# 8bit_reg_v2.net
KiCad netlist of a schematic drawn in Altium Designer
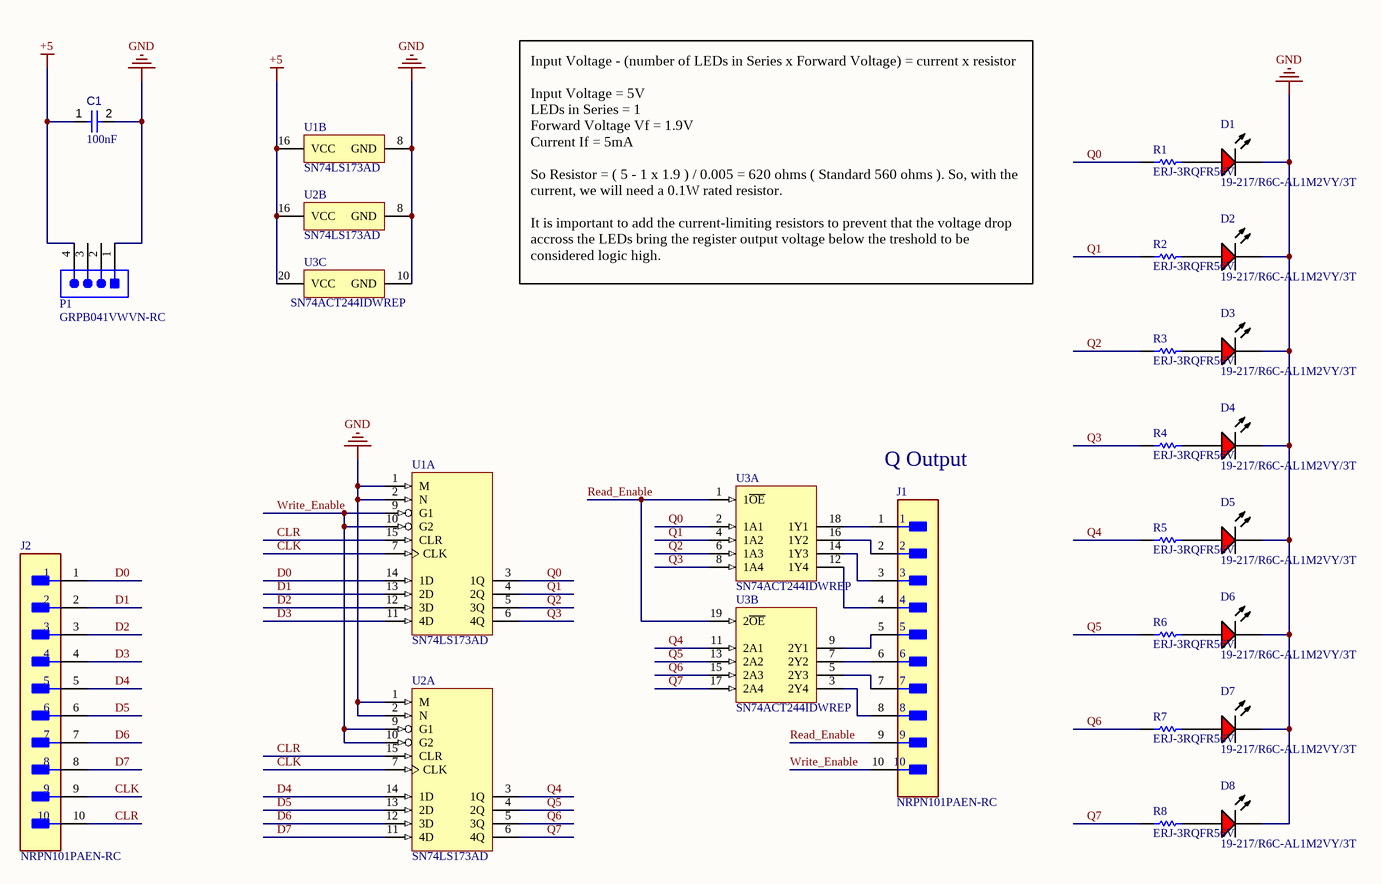
[diagram p0: 8bit_reg_v2.SchDoc]

(export (version "E")
  (design (tool "Eeschema 10.0.6"))
  (components
    (comp (ref "C1")
      (value "100nF")
      (footprint "CAPC1608X90X40NL10T20")
      (description "Chip Capacitor, 100 nF, +/- 10%, 50 V, 0603 (1608 Metric)")
      (fields (field (name "TOLERANCE") "10%") (field (name "Comment") "Capacitor 100 nF +/-10% 50 V 0603"))
      (libsource (lib "GOZ - Altium 365 cloud") (part "CAP-NP-2"))
    )
    (comp (ref "D1")
      (value "19-217/R6C-AL1M2VY/3T")
      (footprint "EVRL-0603-2_V")
      (description "Chip LED, Red, 5 V, 25 mA, -40 to 85 degC, 2-Pin SMD (0603), RoHS, Tape and Reel")
      (fields (field (name "MANUFACTURER") "Everlight Electronics"))
      (libsource (lib "GOZ - Altium 365 cloud") (part "LED-RED-AK-2"))
    )
    (comp (ref "D2")
      (value "19-217/R6C-AL1M2VY/3T")
      (footprint "EVRL-0603-2_V")
      (description "Chip LED, Red, 5 V, 25 mA, -40 to 85 degC, 2-Pin SMD (0603), RoHS, Tape and Reel")
      (fields (field (name "MANUFACTURER") "Everlight Electronics"))
      (libsource (lib "GOZ - Altium 365 cloud") (part "LED-RED-AK-2"))
    )
    (comp (ref "D3")
      (value "19-217/R6C-AL1M2VY/3T")
      (footprint "EVRL-0603-2_V")
      (description "Chip LED, Red, 5 V, 25 mA, -40 to 85 degC, 2-Pin SMD (0603), RoHS, Tape and Reel")
      (fields (field (name "MANUFACTURER") "Everlight Electronics"))
      (libsource (lib "GOZ - Altium 365 cloud") (part "LED-RED-AK-2"))
    )
    (comp (ref "D4")
      (value "19-217/R6C-AL1M2VY/3T")
      (footprint "EVRL-0603-2_V")
      (description "Chip LED, Red, 5 V, 25 mA, -40 to 85 degC, 2-Pin SMD (0603), RoHS, Tape and Reel")
      (fields (field (name "MANUFACTURER") "Everlight Electronics"))
      (libsource (lib "GOZ - Altium 365 cloud") (part "LED-RED-AK-2"))
    )
    (comp (ref "D5")
      (value "19-217/R6C-AL1M2VY/3T")
      (footprint "EVRL-0603-2_V")
      (description "Chip LED, Red, 5 V, 25 mA, -40 to 85 degC, 2-Pin SMD (0603), RoHS, Tape and Reel")
      (fields (field (name "MANUFACTURER") "Everlight Electronics"))
      (libsource (lib "GOZ - Altium 365 cloud") (part "LED-RED-AK-2"))
    )
    (comp (ref "D6")
      (value "19-217/R6C-AL1M2VY/3T")
      (footprint "EVRL-0603-2_V")
      (description "Chip LED, Red, 5 V, 25 mA, -40 to 85 degC, 2-Pin SMD (0603), RoHS, Tape and Reel")
      (fields (field (name "MANUFACTURER") "Everlight Electronics"))
      (libsource (lib "GOZ - Altium 365 cloud") (part "LED-RED-AK-2"))
    )
    (comp (ref "D7")
      (value "19-217/R6C-AL1M2VY/3T")
      (footprint "EVRL-0603-2_V")
      (description "Chip LED, Red, 5 V, 25 mA, -40 to 85 degC, 2-Pin SMD (0603), RoHS, Tape and Reel")
      (fields (field (name "MANUFACTURER") "Everlight Electronics"))
      (libsource (lib "GOZ - Altium 365 cloud") (part "LED-RED-AK-2"))
    )
    (comp (ref "D8")
      (value "19-217/R6C-AL1M2VY/3T")
      (footprint "EVRL-0603-2_V")
      (description "Chip LED, Red, 5 V, 25 mA, -40 to 85 degC, 2-Pin SMD (0603), RoHS, Tape and Reel")
      (fields (field (name "MANUFACTURER") "Everlight Electronics"))
      (libsource (lib "GOZ - Altium 365 cloud") (part "LED-RED-AK-2"))
    )
    (comp (ref "J1")
      (value "NRPN101PAEN-RC")
      (footprint "FP-NRPN101PAEN-RC-MFG")
      (description "CONN HEADER VERT 10POS 2MM")
      (fields
        (field (name "OCTOPART") "https://octopart.com/nrpn101paen-rc-sullins-18674398")
        (field (name "MANUFACTURER") "Sullins")
      )
      (libsource (lib "") (part "aee40dc8b284c03a16094555aa210be_1"))
    )
    (comp (ref "J2")
      (value "NRPN101PAEN-RC")
      (footprint "FP-NRPN101PAEN-RC-MFG")
      (description "CONN HEADER VERT 10POS 2MM")
      (fields
        (field (name "OCTOPART") "https://octopart.com/nrpn101paen-rc-sullins-18674398")
        (field (name "MANUFACTURER") "Sullins")
      )
      (libsource (lib "Altium Content Vault") (part "aee40dc8b284c03a16094555aa210be"))
    )
    (comp (ref "P1")
      (value "GRPB041VWVN-RC")
      (footprint "SLIN-GRPB041VWVN-RC_V")
      (fields (field (name "MANUFACTURER") "Sullins"))
      (libsource (lib "Altium Content Vault") (part "CN-1P-M-R4"))
    )
    (comp (ref "R1")
      (value "ERJ-3RQFR56V")
      (footprint "RESC1608X55X30NL15T15")
      (fields (field (name "MANUFACTURER") "Panasonic"))
      (libsource (lib "Altium Content Vault") (part "RES"))
    )
    (comp (ref "R2")
      (value "ERJ-3RQFR56V")
      (footprint "RESC1608X55X30NL15T15")
      (fields (field (name "MANUFACTURER") "Panasonic"))
      (libsource (lib "Altium Content Vault") (part "RES"))
    )
    (comp (ref "R3")
      (value "ERJ-3RQFR56V")
      (footprint "RESC1608X55X30NL15T15")
      (fields (field (name "MANUFACTURER") "Panasonic"))
      (libsource (lib "Altium Content Vault") (part "RES"))
    )
    (comp (ref "R4")
      (value "ERJ-3RQFR56V")
      (footprint "RESC1608X55X30NL15T15")
      (fields (field (name "MANUFACTURER") "Panasonic"))
      (libsource (lib "Altium Content Vault") (part "RES"))
    )
    (comp (ref "R5")
      (value "ERJ-3RQFR56V")
      (footprint "RESC1608X55X30NL15T15")
      (fields (field (name "MANUFACTURER") "Panasonic"))
      (libsource (lib "Altium Content Vault") (part "RES"))
    )
    (comp (ref "R6")
      (value "ERJ-3RQFR56V")
      (footprint "RESC1608X55X30NL15T15")
      (fields (field (name "MANUFACTURER") "Panasonic"))
      (libsource (lib "Altium Content Vault") (part "RES"))
    )
    (comp (ref "R7")
      (value "ERJ-3RQFR56V")
      (footprint "RESC1608X55X30NL15T15")
      (fields (field (name "MANUFACTURER") "Panasonic"))
      (libsource (lib "Altium Content Vault") (part "RES"))
    )
    (comp (ref "R8")
      (value "ERJ-3RQFR56V")
      (footprint "RESC1608X55X30NL15T15")
      (fields (field (name "MANUFACTURER") "Panasonic"))
      (libsource (lib "Altium Content Vault") (part "RES"))
    )
    (comp (ref "U1")
      (value "SN74LS173AD")
      (footprint "D0016A_M")
      (description "TEXAS INSTRUMENTS SN74LS173AD Flip-Flop, D, 17 ns, 50 MHz, 24 mA, SOIC, 16 Pins")
      (libsource (lib "GOZ - Altium 365 cloud") (part "TI-SNX4XX173X-16"))
    )
    (comp (ref "U2")
      (value "SN74LS173AD")
      (footprint "D0016A_M")
      (description "TEXAS INSTRUMENTS SN74LS173AD Flip-Flop, D, 17 ns, 50 MHz, 24 mA, SOIC, 16 Pins")
      (libsource (lib "GOZ - Altium 365 cloud") (part "TI-SNX4XX173X-16"))
    )
    (comp (ref "U3")
      (value "SN74ACT244IDWREP")
      (footprint "DW0020A_L")
      (description "Enhanced Product Octal Buffers/Drivers With 3-State Outputs, DW0020A, LARGE T&R")
      (fields
        (field (name "GENERIC PART NUMBER") "SN74ACT244-EP")
        (field (name "MANUFACTURER") "Texas Instruments")
      )
      (libsource (lib "SN74ACT244IDWREP") (part "CMP-0440-00699-3"))
    )
  )
  (nets
    (net (code "1") (name "+5") (class "Default")
      (node (ref "C1") (pin "1") (pinfunction "1_1") (pintype "passive"))
      (node (ref "P1") (pin "4") (pinfunction "4_4") (pintype "passive"))
      (node (ref "U1") (pin "16") (pinfunction "VCC_16") (pintype "power_in"))
      (node (ref "U2") (pin "16") (pinfunction "VCC_16") (pintype "power_in"))
      (node (ref "U3") (pin "20") (pinfunction "VCC_20") (pintype "power_in"))
    )
    (net (code "2") (name "/CLK") (class "Default")
      (node (ref "J2") (pin "9") (pinfunction "9_9") (pintype "passive"))
      (node (ref "U1") (pin "7") (pinfunction "CLK_7") (pintype "input"))
      (node (ref "U2") (pin "7") (pinfunction "CLK_7") (pintype "input"))
    )
    (net (code "3") (name "/CLR") (class "Default")
      (node (ref "J2") (pin "10") (pinfunction "10_10") (pintype "passive"))
      (node (ref "U1") (pin "15") (pinfunction "CLR_15") (pintype "input"))
      (node (ref "U2") (pin "15") (pinfunction "CLR_15") (pintype "input"))
    )
    (net (code "4") (name "/D0") (class "Default")
      (node (ref "J2") (pin "1") (pinfunction "1_1") (pintype "passive"))
      (node (ref "U1") (pin "14") (pinfunction "1D_14") (pintype "input"))
    )
    (net (code "5") (name "/D1") (class "Default")
      (node (ref "J2") (pin "2") (pinfunction "2_2") (pintype "passive"))
      (node (ref "U1") (pin "13") (pinfunction "2D_13") (pintype "input"))
    )
    (net (code "6") (name "/D2") (class "Default")
      (node (ref "J2") (pin "3") (pinfunction "3_3") (pintype "passive"))
      (node (ref "U1") (pin "12") (pinfunction "3D_12") (pintype "input"))
    )
    (net (code "7") (name "/D3") (class "Default")
      (node (ref "J2") (pin "4") (pinfunction "4_4") (pintype "passive"))
      (node (ref "U1") (pin "11") (pinfunction "4D_11") (pintype "input"))
    )
    (net (code "8") (name "/D4") (class "Default")
      (node (ref "J2") (pin "5") (pinfunction "5_5") (pintype "passive"))
      (node (ref "U2") (pin "14") (pinfunction "1D_14") (pintype "input"))
    )
    (net (code "9") (name "/D5") (class "Default")
      (node (ref "J2") (pin "6") (pinfunction "6_6") (pintype "passive"))
      (node (ref "U2") (pin "13") (pinfunction "2D_13") (pintype "input"))
    )
    (net (code "10") (name "/D6") (class "Default")
      (node (ref "J2") (pin "7") (pinfunction "7_7") (pintype "passive"))
      (node (ref "U2") (pin "12") (pinfunction "3D_12") (pintype "input"))
    )
    (net (code "11") (name "/D7") (class "Default")
      (node (ref "J2") (pin "8") (pinfunction "8_8") (pintype "passive"))
      (node (ref "U2") (pin "11") (pinfunction "4D_11") (pintype "input"))
    )
    (net (code "12") (name "/Q0") (class "Default")
      (node (ref "R1") (pin "1") (pinfunction "1_1") (pintype "passive"))
      (node (ref "U1") (pin "3") (pinfunction "1Q_3") (pintype "tri_state"))
      (node (ref "U3") (pin "2") (pinfunction "1A1_2") (pintype "input"))
    )
    (net (code "13") (name "/Q1") (class "Default")
      (node (ref "R2") (pin "1") (pinfunction "1_1") (pintype "passive"))
      (node (ref "U1") (pin "4") (pinfunction "2Q_4") (pintype "tri_state"))
      (node (ref "U3") (pin "4") (pinfunction "1A2_4") (pintype "input"))
    )
    (net (code "14") (name "/Q2") (class "Default")
      (node (ref "R3") (pin "1") (pinfunction "1_1") (pintype "passive"))
      (node (ref "U1") (pin "5") (pinfunction "3Q_5") (pintype "tri_state"))
      (node (ref "U3") (pin "6") (pinfunction "1A3_6") (pintype "input"))
    )
    (net (code "15") (name "/Q3") (class "Default")
      (node (ref "R4") (pin "1") (pinfunction "1_1") (pintype "passive"))
      (node (ref "U1") (pin "6") (pinfunction "4Q_6") (pintype "tri_state"))
      (node (ref "U3") (pin "8") (pinfunction "1A4_8") (pintype "input"))
    )
    (net (code "16") (name "/Q4") (class "Default")
      (node (ref "R5") (pin "1") (pinfunction "1_1") (pintype "passive"))
      (node (ref "U2") (pin "3") (pinfunction "1Q_3") (pintype "tri_state"))
      (node (ref "U3") (pin "11") (pinfunction "2A1_11") (pintype "input"))
    )
    (net (code "17") (name "/Q5") (class "Default")
      (node (ref "R6") (pin "1") (pinfunction "1_1") (pintype "passive"))
      (node (ref "U2") (pin "4") (pinfunction "2Q_4") (pintype "tri_state"))
      (node (ref "U3") (pin "13") (pinfunction "2A2_13") (pintype "input"))
    )
    (net (code "18") (name "/Q6") (class "Default")
      (node (ref "R7") (pin "1") (pinfunction "1_1") (pintype "passive"))
      (node (ref "U2") (pin "5") (pinfunction "3Q_5") (pintype "tri_state"))
      (node (ref "U3") (pin "15") (pinfunction "2A3_15") (pintype "input"))
    )
    (net (code "19") (name "/Q7") (class "Default")
      (node (ref "R8") (pin "1") (pinfunction "1_1") (pintype "passive"))
      (node (ref "U2") (pin "6") (pinfunction "4Q_6") (pintype "tri_state"))
      (node (ref "U3") (pin "17") (pinfunction "2A4_17") (pintype "input"))
    )
    (net (code "20") (name "/Read_Enable") (class "Default")
      (node (ref "J1") (pin "9") (pinfunction "9_9") (pintype "passive"))
      (node (ref "U3") (pin "1") (pinfunction "1~{OE}_1") (pintype "input"))
      (node (ref "U3") (pin "19") (pinfunction "2~{OE}_19") (pintype "input"))
    )
    (net (code "21") (name "/Write_Enable") (class "Default")
      (node (ref "J1") (pin "10") (pinfunction "10_10") (pintype "passive"))
      (node (ref "U1") (pin "10") (pinfunction "G2_10") (pintype "input"))
      (node (ref "U1") (pin "9") (pinfunction "G1_9") (pintype "input"))
      (node (ref "U2") (pin "10") (pinfunction "G2_10") (pintype "input"))
      (node (ref "U2") (pin "9") (pinfunction "G1_9") (pintype "input"))
    )
    (net (code "22") (name "GND") (class "Default")
      (node (ref "C1") (pin "2") (pinfunction "2_2") (pintype "passive"))
      (node (ref "D1") (pin "2") (pinfunction "K_2") (pintype "passive"))
      (node (ref "D2") (pin "2") (pinfunction "K_2") (pintype "passive"))
      (node (ref "D3") (pin "2") (pinfunction "K_2") (pintype "passive"))
      (node (ref "D4") (pin "2") (pinfunction "K_2") (pintype "passive"))
      (node (ref "D5") (pin "2") (pinfunction "K_2") (pintype "passive"))
      (node (ref "D6") (pin "2") (pinfunction "K_2") (pintype "passive"))
      (node (ref "D7") (pin "2") (pinfunction "K_2") (pintype "passive"))
      (node (ref "D8") (pin "2") (pinfunction "K_2") (pintype "passive"))
      (node (ref "P1") (pin "1") (pinfunction "1_1") (pintype "passive"))
      (node (ref "U1") (pin "1") (pinfunction "M_1") (pintype "input"))
      (node (ref "U1") (pin "2") (pinfunction "N_2") (pintype "input"))
      (node (ref "U1") (pin "8") (pinfunction "GND_8") (pintype "power_in"))
      (node (ref "U2") (pin "1") (pinfunction "M_1") (pintype "input"))
      (node (ref "U2") (pin "2") (pinfunction "N_2") (pintype "input"))
      (node (ref "U2") (pin "8") (pinfunction "GND_8") (pintype "power_in"))
      (node (ref "U3") (pin "10") (pinfunction "GND_10") (pintype "power_in"))
    )
    (net (code "23") (name "Net-(D1-A)") (class "Default")
      (node (ref "D1") (pin "1") (pinfunction "A_1") (pintype "passive"))
      (node (ref "R1") (pin "2") (pinfunction "2_2") (pintype "passive"))
    )
    (net (code "24") (name "Net-(D2-A)") (class "Default")
      (node (ref "D2") (pin "1") (pinfunction "A_1") (pintype "passive"))
      (node (ref "R2") (pin "2") (pinfunction "2_2") (pintype "passive"))
    )
    (net (code "25") (name "Net-(D3-A)") (class "Default")
      (node (ref "D3") (pin "1") (pinfunction "A_1") (pintype "passive"))
      (node (ref "R3") (pin "2") (pinfunction "2_2") (pintype "passive"))
    )
    (net (code "26") (name "Net-(D4-A)") (class "Default")
      (node (ref "D4") (pin "1") (pinfunction "A_1") (pintype "passive"))
      (node (ref "R4") (pin "2") (pinfunction "2_2") (pintype "passive"))
    )
    (net (code "27") (name "Net-(D5-A)") (class "Default")
      (node (ref "D5") (pin "1") (pinfunction "A_1") (pintype "passive"))
      (node (ref "R5") (pin "2") (pinfunction "2_2") (pintype "passive"))
    )
    (net (code "28") (name "Net-(D6-A)") (class "Default")
      (node (ref "D6") (pin "1") (pinfunction "A_1") (pintype "passive"))
      (node (ref "R6") (pin "2") (pinfunction "2_2") (pintype "passive"))
    )
    (net (code "29") (name "Net-(D7-A)") (class "Default")
      (node (ref "D7") (pin "1") (pinfunction "A_1") (pintype "passive"))
      (node (ref "R7") (pin "2") (pinfunction "2_2") (pintype "passive"))
    )
    (net (code "30") (name "Net-(D8-A)") (class "Default")
      (node (ref "D8") (pin "1") (pinfunction "A_1") (pintype "passive"))
      (node (ref "R8") (pin "2") (pinfunction "2_2") (pintype "passive"))
    )
    (net (code "31") (name "Net-(U3A-1Y1)") (class "Default")
      (node (ref "J1") (pin "1") (pinfunction "1_1") (pintype "passive"))
      (node (ref "U3") (pin "18") (pinfunction "1Y1_18") (pintype "tri_state"))
    )
    (net (code "32") (name "Net-(U3A-1Y2)") (class "Default")
      (node (ref "J1") (pin "2") (pinfunction "2_2") (pintype "passive"))
      (node (ref "U3") (pin "16") (pinfunction "1Y2_16") (pintype "tri_state"))
    )
    (net (code "33") (name "Net-(U3A-1Y3)") (class "Default")
      (node (ref "J1") (pin "3") (pinfunction "3_3") (pintype "passive"))
      (node (ref "U3") (pin "14") (pinfunction "1Y3_14") (pintype "tri_state"))
    )
    (net (code "34") (name "Net-(U3A-1Y4)") (class "Default")
      (node (ref "J1") (pin "4") (pinfunction "4_4") (pintype "passive"))
      (node (ref "U3") (pin "12") (pinfunction "1Y4_12") (pintype "tri_state"))
    )
    (net (code "35") (name "Net-(U3B-2Y1)") (class "Default")
      (node (ref "J1") (pin "5") (pinfunction "5_5") (pintype "passive"))
      (node (ref "U3") (pin "9") (pinfunction "2Y1_9") (pintype "tri_state"))
    )
    (net (code "36") (name "Net-(U3B-2Y2)") (class "Default")
      (node (ref "J1") (pin "6") (pinfunction "6_6") (pintype "passive"))
      (node (ref "U3") (pin "7") (pinfunction "2Y2_7") (pintype "tri_state"))
    )
    (net (code "37") (name "Net-(U3B-2Y3)") (class "Default")
      (node (ref "J1") (pin "7") (pinfunction "7_7") (pintype "passive"))
      (node (ref "U3") (pin "5") (pinfunction "2Y3_5") (pintype "tri_state"))
    )
    (net (code "38") (name "Net-(U3B-2Y4)") (class "Default")
      (node (ref "J1") (pin "8") (pinfunction "8_8") (pintype "passive"))
      (node (ref "U3") (pin "3") (pinfunction "2Y4_3") (pintype "tri_state"))
    )
    (net (code "39") (name "unconnected-(P1-Pad2)") (class "Default")
      (node (ref "P1") (pin "2") (pinfunction "2_2") (pintype "passive"))
    )
    (net (code "40") (name "unconnected-(P1-Pad3)") (class "Default")
      (node (ref "P1") (pin "3") (pinfunction "3_3") (pintype "passive"))
    )
  )
)
